# HMC194A.net
KiCad netlist of a schematic drawn in Altium Designer
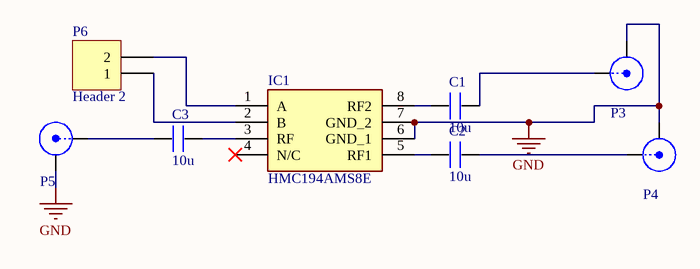
[diagram p0: HMC194A.SchDoc]

(export (version "E")
  (design (tool "Eeschema 10.0.6"))
  (components
    (comp (ref "C1")
      (value "10u")
      (footprint "0402")
      (description "Capacitor")
      (libsource (lib "MYLIB") (part "C"))
    )
    (comp (ref "C2")
      (value "10u")
      (footprint "0402")
      (description "Capacitor")
      (libsource (lib "MYLIB") (part "C"))
    )
    (comp (ref "C3")
      (value "10u")
      (footprint "0402")
      (description "Capacitor")
      (libsource (lib "MYLIB") (part "C"))
    )
    (comp (ref "IC1")
      (value "HMC194AMS8E")
      (footprint "MYLIB:SOP65P488X110-8N")
      (description "Integrated Circuit")
      (fields (field (name "MOUSER PART NUMBER") "584-HMC194AMS8E"))
      (libsource (lib "MYLIB") (part "HMC194AMS8E"))
    )
    (comp (ref "P3")
      (value "SMA")
      (footprint "SMA")
      (description "SMA Connector")
      (libsource (lib "MYLIB") (part "SMA"))
    )
    (comp (ref "P4")
      (value "SMA")
      (footprint "SMA")
      (description "SMA Connector")
      (libsource (lib "MYLIB") (part "SMA"))
    )
    (comp (ref "P5")
      (value "SMA")
      (footprint "SMA")
      (description "SMA Connector")
      (libsource (lib "MYLIB") (part "SMA"))
    )
    (comp (ref "P6")
      (value "Header 2")
      (footprint "HDR1X2")
      (description "Header, 2-Pin")
      (fields (field (name "PUBLISHER") "Altium Limited"))
      (libsource (lib "MYLIB") (part "Header 2"))
    )
  )
  (nets
    (net (code "1") (name "GND") (class "Default")
      (node (ref "IC1") (pin "6") (pinfunction "GND_1_6") (pintype "passive"))
      (node (ref "IC1") (pin "7") (pinfunction "GND_2_7") (pintype "passive"))
      (node (ref "P3") (pin "2") (pinfunction "Y_2") (pintype "passive"))
      (node (ref "P4") (pin "2") (pinfunction "Y_2") (pintype "passive"))
      (node (ref "P5") (pin "2") (pinfunction "Y_2") (pintype "passive"))
    )
    (net (code "2") (name "Net-(IC1-A)") (class "Default")
      (node (ref "IC1") (pin "1") (pinfunction "A_1") (pintype "passive"))
      (node (ref "P6") (pin "2") (pinfunction "2_2") (pintype "passive"))
    )
    (net (code "3") (name "Net-(IC1-B)") (class "Default")
      (node (ref "IC1") (pin "2") (pinfunction "B_2") (pintype "passive"))
      (node (ref "P6") (pin "1") (pinfunction "1_1") (pintype "passive"))
    )
    (net (code "4") (name "Net-(IC1-RF)") (class "Default")
      (node (ref "C3") (pin "2") (pintype "passive"))
      (node (ref "IC1") (pin "3") (pinfunction "RF_3") (pintype "passive"))
    )
    (net (code "5") (name "Net-(IC1-RF1)") (class "Default")
      (node (ref "C2") (pin "1") (pintype "passive"))
      (node (ref "IC1") (pin "5") (pinfunction "RF1_5") (pintype "passive"))
    )
    (net (code "6") (name "Net-(IC1-RF2)") (class "Default")
      (node (ref "C1") (pin "1") (pintype "passive"))
      (node (ref "IC1") (pin "8") (pinfunction "RF2_8") (pintype "passive"))
    )
    (net (code "7") (name "Net-(P3-X)") (class "Default")
      (node (ref "C1") (pin "2") (pintype "passive"))
      (node (ref "P3") (pin "1") (pinfunction "X_1") (pintype "passive"))
    )
    (net (code "8") (name "Net-(P4-X)") (class "Default")
      (node (ref "C2") (pin "2") (pintype "passive"))
      (node (ref "P4") (pin "1") (pinfunction "X_1") (pintype "passive"))
    )
    (net (code "9") (name "Net-(P5-X)") (class "Default")
      (node (ref "C3") (pin "1") (pintype "passive"))
      (node (ref "P5") (pin "1") (pinfunction "X_1") (pintype "passive"))
    )
    (net (code "10") (name "unconnected-(IC1-N{slash}C-Pad4)") (class "Default")
      (node (ref "IC1") (pin "4") (pinfunction "N/C_4") (pintype "passive+no_connect"))
    )
  )
)
